# sensor_board_v0_51.net
KiCad netlist of a schematic drawn in EAGLE
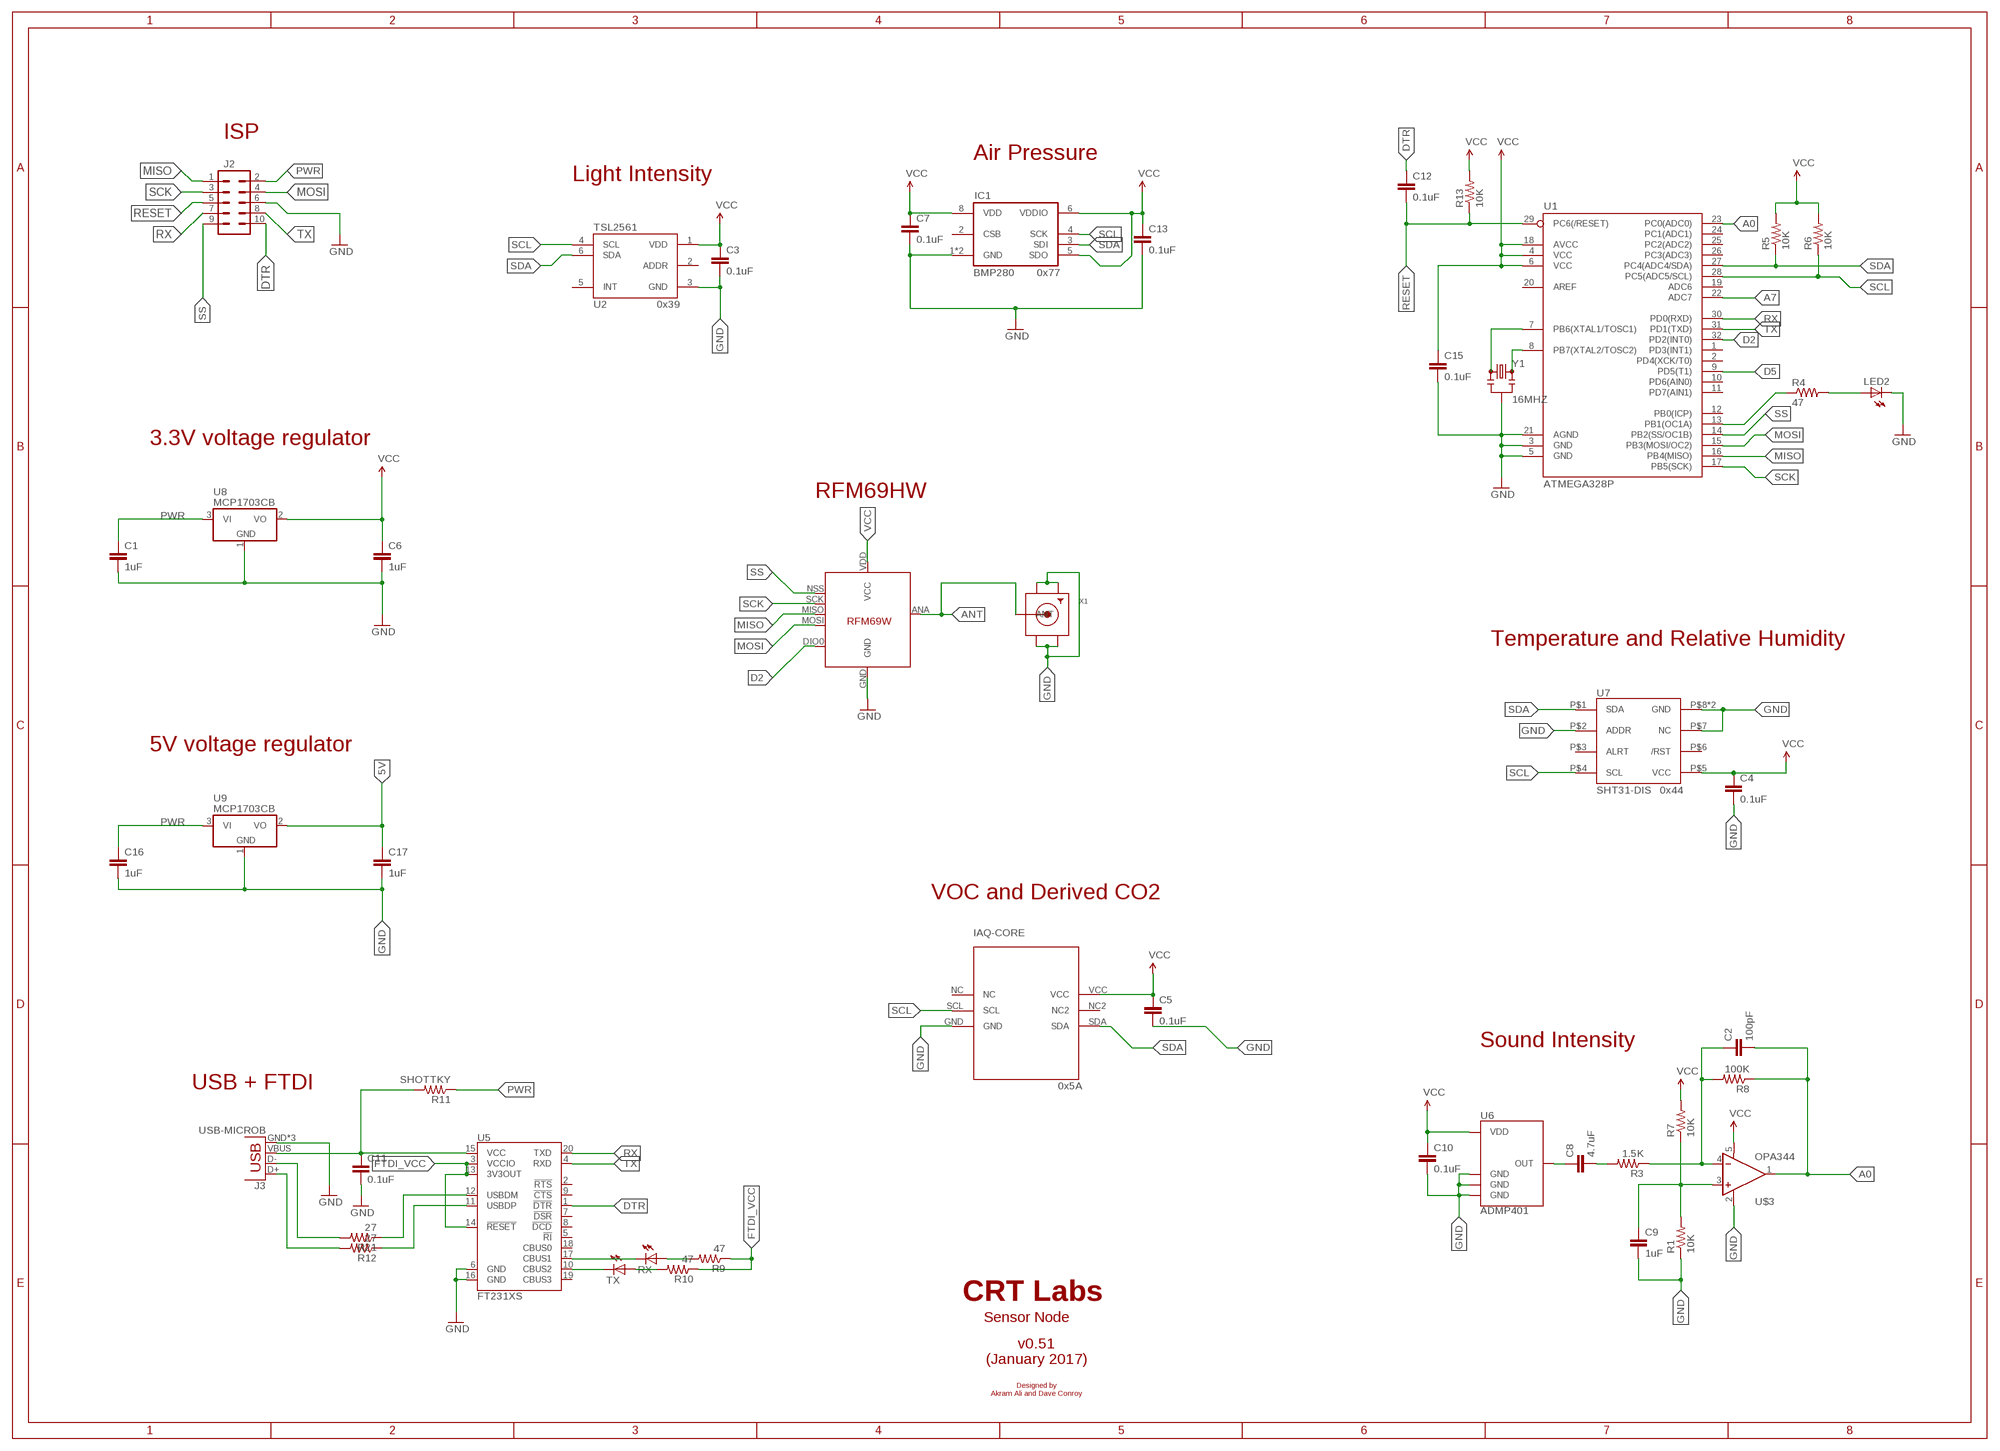
[diagram p0: schematic, sheet 1]

(export (version "E")
  (design (tool "Eeschema 10.0.6"))
  (components
    (comp (ref "C1")
      (value "1uF")
      (footprint "eagle-import:0805")
      (libsource (lib "eagle-import") (part "CAP0805"))
    )
    (comp (ref "C2")
      (value "100pF")
      (footprint "eagle-import:0805")
      (libsource (lib "eagle-import") (part "CAP0805"))
    )
    (comp (ref "C3")
      (value "0.1uF")
      (footprint "eagle-import:0805")
      (libsource (lib "eagle-import") (part "SparkFun-Passives_CAP0805"))
    )
    (comp (ref "C4")
      (value "0.1uF")
      (footprint "eagle-import:0805")
      (libsource (lib "eagle-import") (part "SparkFun-Passives_CAP0805"))
    )
    (comp (ref "C5")
      (value "0.1uF")
      (footprint "eagle-import:0805")
      (libsource (lib "eagle-import") (part "SparkFun-Passives_CAP0805"))
    )
    (comp (ref "C6")
      (value "1uF")
      (footprint "eagle-import:0805")
      (libsource (lib "eagle-import") (part "CAP0805"))
    )
    (comp (ref "C7")
      (value "0.1uF")
      (footprint "eagle-import:0805")
      (libsource (lib "eagle-import") (part "SparkFun-Passives_CAP0805"))
    )
    (comp (ref "C8")
      (value "4.7uF")
      (footprint "eagle-import:0805")
      (libsource (lib "eagle-import") (part "CAP0805"))
    )
    (comp (ref "C9")
      (value "1uF")
      (footprint "eagle-import:0805")
      (libsource (lib "eagle-import") (part "CAP0805"))
    )
    (comp (ref "C10")
      (value "0.1uF")
      (footprint "eagle-import:0805")
      (libsource (lib "eagle-import") (part "CAP0805"))
    )
    (comp (ref "C11")
      (value "0.1uF")
      (footprint "eagle-import:0805")
      (libsource (lib "eagle-import") (part "CAP0805"))
    )
    (comp (ref "C12")
      (value "0.1uF")
      (footprint "eagle-import:0805")
      (libsource (lib "eagle-import") (part "SparkFun-Passives_CAP0805"))
    )
    (comp (ref "C13")
      (value "0.1uF")
      (footprint "eagle-import:0805")
      (libsource (lib "eagle-import") (part "SparkFun-Passives_CAP0805"))
    )
    (comp (ref "C15")
      (value "0.1uF")
      (footprint "eagle-import:0805")
      (libsource (lib "eagle-import") (part "SparkFun-Passives_CAP0805"))
    )
    (comp (ref "C16")
      (value "1uF")
      (footprint "eagle-import:0805")
      (libsource (lib "eagle-import") (part "CAP0805"))
    )
    (comp (ref "C17")
      (value "1uF")
      (footprint "eagle-import:0805")
      (libsource (lib "eagle-import") (part "CAP0805"))
    )
    (comp (ref "IAQ-CORE")
      (value "IAQ-CORE")
      (footprint "eagle-import:IAQ-CORE")
      (fields (field (name "MPN") "IAQ CORE"))
      (libsource (lib "eagle-import") (part "IAQ-CORE"))
    )
    (comp (ref "IC1")
      (value "BMP280")
      (footprint "eagle-import:BMP280")
      (libsource (lib "eagle-import") (part "BMP280"))
    )
    (comp (ref "J2")
      (value "M05X2PTH")
      (footprint "eagle-import:AVR_ICSP")
      (libsource (lib "eagle-import") (part "M05X2PTH"))
    )
    (comp (ref "J3")
      (value "USB-MICROB")
      (footprint "eagle-import:USB-MICROB")
      (libsource (lib "eagle-import") (part "USB-MICROB"))
    )
    (comp (ref "LED2")
      (value "LEDCHIPLED_0805")
      (footprint "eagle-import:CHIPLED_0805")
      (libsource (lib "eagle-import") (part "LEDCHIPLED_0805"))
    )
    (comp (ref "R1")
      (value "10K")
      (footprint "eagle-import:0805")
      (libsource (lib "eagle-import") (part "RESISTOR0805-RES"))
    )
    (comp (ref "R3")
      (value "1.5K")
      (footprint "eagle-import:0805")
      (libsource (lib "eagle-import") (part "RESISTOR0805-RES"))
    )
    (comp (ref "R4")
      (value "47")
      (footprint "eagle-import:0805")
      (libsource (lib "eagle-import") (part "SparkFun-Resistors_RESISTOR0805-RES"))
    )
    (comp (ref "R5")
      (value "10K")
      (footprint "eagle-import:0805")
      (libsource (lib "eagle-import") (part "SparkFun-Resistors_RESISTOR0805-RES"))
    )
    (comp (ref "R6")
      (value "10K")
      (footprint "eagle-import:0805")
      (libsource (lib "eagle-import") (part "SparkFun-Resistors_RESISTOR0805-RES"))
    )
    (comp (ref "R7")
      (value "10K")
      (footprint "eagle-import:0805")
      (libsource (lib "eagle-import") (part "RESISTOR0805-RES"))
    )
    (comp (ref "R8")
      (value "100K")
      (footprint "eagle-import:0805")
      (libsource (lib "eagle-import") (part "RESISTOR0805-RES"))
    )
    (comp (ref "R9")
      (value "47")
      (footprint "eagle-import:0805")
      (libsource (lib "eagle-import") (part "RESISTOR0805-RES"))
    )
    (comp (ref "R10")
      (value "47")
      (footprint "eagle-import:0805")
      (libsource (lib "eagle-import") (part "RESISTOR0805-RES"))
    )
    (comp (ref "R11")
      (value "SHOTTKY")
      (footprint "eagle-import:0805")
      (libsource (lib "eagle-import") (part "RESISTOR0805-RES"))
    )
    (comp (ref "R12")
      (value "27")
      (footprint "eagle-import:0805")
      (libsource (lib "eagle-import") (part "RESISTOR0805-RES"))
    )
    (comp (ref "R13")
      (value "10K")
      (footprint "eagle-import:0805")
      (libsource (lib "eagle-import") (part "RESISTOR0805-RES"))
    )
    (comp (ref "R21")
      (value "27")
      (footprint "eagle-import:0805")
      (libsource (lib "eagle-import") (part "RESISTOR0805-RES"))
    )
    (comp (ref "RX")
      (value "LEDCHIPLED_0805")
      (footprint "eagle-import:CHIPLED_0805")
      (libsource (lib "eagle-import") (part "LEDCHIPLED_0805"))
    )
    (comp (ref "TX")
      (value "LEDCHIPLED_0805")
      (footprint "eagle-import:CHIPLED_0805")
      (libsource (lib "eagle-import") (part "LEDCHIPLED_0805"))
    )
    (comp (ref "U$3")
      (value "OPA344")
      (footprint "eagle-import:SOT23-5")
      (libsource (lib "eagle-import") (part "OPA344"))
    )
    (comp (ref "U$4")
      (value "RFM69HW")
      (footprint "eagle-import:LOWPOWERLAB_RFM69W-MINPADS")
      (libsource (lib "eagle-import") (part "LOWPOWERLAB_RFM69"))
    )
    (comp (ref "U1")
      (value "ATMEGA328P")
      (footprint "eagle-import:TQFP32-08")
      (fields (field (name "MPN") "ATMEGA328PB-AU"))
      (libsource (lib "eagle-import") (part "ATMEGA328P_TQFP"))
    )
    (comp (ref "U2")
      (value "TSL2561")
      (footprint "eagle-import:FN-6")
      (fields (field (name "MANF") "AMS-TAOS-USA-Inc.") (field (name "MPN") "TSL2561FN"))
      (libsource (lib "eagle-import") (part "TSL2561FN"))
    )
    (comp (ref "U5")
      (value "FT231XS")
      (footprint "eagle-import:SSOP20_L")
      (libsource (lib "eagle-import") (part "FT231XS"))
    )
    (comp (ref "U6")
      (value "ADMP401")
      (footprint "eagle-import:ADMP401")
      (libsource (lib "eagle-import") (part "ADMP401"))
    )
    (comp (ref "U7")
      (value "SHT31-DIS")
      (footprint "eagle-import:SHT3X")
      (fields (field (name "MPN") "SHT31-DIS-B"))
      (libsource (lib "eagle-import") (part "SHT31-DIS"))
    )
    (comp (ref "U8")
      (value "MCP1703CB")
      (footprint "eagle-import:SOT23")
      (fields (field (name "MPN") "MCP1703T-2502E/CB"))
      (libsource (lib "eagle-import") (part "MCP1703CB"))
    )
    (comp (ref "U9")
      (value "MCP1703CB")
      (footprint "eagle-import:SOT23")
      (fields (field (name "MPN") "MCP1703T-2502E/CB"))
      (libsource (lib "eagle-import") (part "MCP1703CB"))
    )
    (comp (ref "X1")
      (value "SMACONNECTOR_EDGE")
      (footprint "eagle-import:SMA_EDGELAUNCH")
      (libsource (lib "eagle-import") (part "SMACONNECTOR_EDGE"))
    )
    (comp (ref "Y1")
      (value "16MHZ")
      (footprint "eagle-import:RESONATOR-SMD")
      (libsource (lib "eagle-import") (part "RESONATOR16MHZ"))
    )
  )
  (nets
    (net (code "1") (name "5V") (class "Default")
      (node (ref "C17") (pin "1") (pinfunction "1_1") (pintype "passive"))
      (node (ref "U9") (pin "2") (pinfunction "VO_2") (pintype "passive"))
    )
    (net (code "2") (name "A0") (class "Default")
      (node (ref "C2") (pin "2") (pinfunction "2_2") (pintype "passive"))
      (node (ref "R8") (pin "1") (pinfunction "1_1") (pintype "passive"))
      (node (ref "U$3") (pin "1") (pinfunction "OUT_1") (pintype "output"))
      (node (ref "U1") (pin "23") (pinfunction "PC0(ADC0)_23") (pintype "bidirectional"))
    )
    (net (code "3") (name "A7") (class "Default")
      (node (ref "U1") (pin "22") (pinfunction "ADC7_22") (pintype "bidirectional"))
    )
    (net (code "4") (name "ANT") (class "Default")
      (node (ref "U$4") (pin "ANA") (pinfunction "ANT_ANA") (pintype "passive"))
      (node (ref "X1") (pin "P") (pinfunction "ANT_P") (pintype "bidirectional"))
    )
    (net (code "5") (name "D2") (class "Default")
      (node (ref "U$4") (pin "DIO0") (pinfunction "DIO0_DIO0") (pintype "open_collector"))
      (node (ref "U1") (pin "32") (pinfunction "PD2(INT0)_32") (pintype "bidirectional"))
    )
    (net (code "6") (name "D5") (class "Default")
      (node (ref "U1") (pin "9") (pinfunction "PD5(T1)_9") (pintype "bidirectional"))
    )
    (net (code "7") (name "DTR") (class "Default")
      (node (ref "C12") (pin "1") (pinfunction "1_1") (pintype "passive"))
      (node (ref "J2") (pin "10") (pinfunction "10_10") (pintype "passive"))
      (node (ref "U5") (pin "1") (pinfunction "~{DTR}_1") (pintype "bidirectional"))
    )
    (net (code "8") (name "FTDI_VCC") (class "Default")
      (node (ref "R10") (pin "1") (pinfunction "1_1") (pintype "passive"))
      (node (ref "R9") (pin "1") (pinfunction "1_1") (pintype "passive"))
      (node (ref "U5") (pin "13") (pinfunction "3V3OUT_13") (pintype "bidirectional"))
      (node (ref "U5") (pin "14") (pinfunction "~{RESET}_14") (pintype "bidirectional"))
      (node (ref "U5") (pin "3") (pinfunction "VCCIO_3") (pintype "bidirectional"))
    )
    (net (code "9") (name "GND") (class "Default")
      (node (ref "C1") (pin "2") (pinfunction "2_2") (pintype "passive"))
      (node (ref "C10") (pin "2") (pinfunction "2_2") (pintype "passive"))
      (node (ref "C11") (pin "2") (pinfunction "2_2") (pintype "passive"))
      (node (ref "C13") (pin "2") (pinfunction "2_2") (pintype "passive"))
      (node (ref "C15") (pin "2") (pinfunction "2_2") (pintype "passive"))
      (node (ref "C16") (pin "2") (pinfunction "2_2") (pintype "passive"))
      (node (ref "C17") (pin "2") (pinfunction "2_2") (pintype "passive"))
      (node (ref "C3") (pin "2") (pinfunction "2_2") (pintype "passive"))
      (node (ref "C4") (pin "2") (pinfunction "2_2") (pintype "passive"))
      (node (ref "C5") (pin "2") (pinfunction "2_2") (pintype "passive"))
      (node (ref "C6") (pin "2") (pinfunction "2_2") (pintype "passive"))
      (node (ref "C7") (pin "2") (pinfunction "2_2") (pintype "passive"))
      (node (ref "C9") (pin "2") (pinfunction "2_2") (pintype "passive"))
      (node (ref "IAQ-CORE") (pin "GND") (pinfunction "GND_GND") (pintype "bidirectional"))
      (node (ref "IC1") (pin "1") (pinfunction "GND_1") (pintype "power_in"))
      (node (ref "IC1") (pin "7") (pinfunction "GND_7") (pintype "power_in"))
      (node (ref "J2") (pin "6") (pinfunction "6_6") (pintype "passive"))
      (node (ref "J3") (pin "GND") (pinfunction "GND_GND") (pintype "bidirectional"))
      (node (ref "J3") (pin "MT1") (pinfunction "GND_MT1") (pintype "bidirectional"))
      (node (ref "J3") (pin "MT2") (pinfunction "GND_MT2") (pintype "bidirectional"))
      (node (ref "LED2") (pin "C") (pinfunction "C_C") (pintype "passive"))
      (node (ref "R1") (pin "1") (pinfunction "1_1") (pintype "passive"))
      (node (ref "U$3") (pin "2") (pinfunction "V-_2") (pintype "power_in"))
      (node (ref "U$4") (pin "GND") (pinfunction "GND_GND") (pintype "power_in"))
      (node (ref "U1") (pin "21") (pinfunction "AGND_21") (pintype "bidirectional"))
      (node (ref "U1") (pin "3") (pinfunction "GND_3") (pintype "bidirectional"))
      (node (ref "U1") (pin "5") (pinfunction "GND_5") (pintype "bidirectional"))
      (node (ref "U2") (pin "3") (pinfunction "GND_3") (pintype "power_in"))
      (node (ref "U5") (pin "16") (pinfunction "GND_16") (pintype "bidirectional"))
      (node (ref "U5") (pin "6") (pinfunction "GND_6") (pintype "bidirectional"))
      (node (ref "U6") (pin "2") (pinfunction "GND_2") (pintype "bidirectional"))
      (node (ref "U6") (pin "4") (pinfunction "GND_4") (pintype "bidirectional"))
      (node (ref "U6") (pin "6") (pinfunction "GND_6") (pintype "bidirectional"))
      (node (ref "U7") (pin "P$2") (pinfunction "ADDR_P$2") (pintype "bidirectional"))
      (node (ref "U7") (pin "P$7") (pinfunction "NC_P$7") (pintype "bidirectional"))
      (node (ref "U7") (pin "P$8") (pinfunction "GND_P$8") (pintype "bidirectional"))
      (node (ref "U7") (pin "PAD") (pinfunction "GND_PAD") (pintype "bidirectional"))
      (node (ref "U8") (pin "1") (pinfunction "GND_1") (pintype "passive"))
      (node (ref "U9") (pin "1") (pinfunction "GND_1") (pintype "passive"))
      (node (ref "X1") (pin "GND@1") (pinfunction "GND4_GND@1") (pintype "power_in"))
      (node (ref "X1") (pin "GND@2") (pinfunction "GND3_GND@2") (pintype "power_in"))
      (node (ref "X1") (pin "GND@3") (pinfunction "GND2_GND@3") (pintype "power_in"))
      (node (ref "X1") (pin "GND@4") (pinfunction "GND1_GND@4") (pintype "power_in"))
      (node (ref "Y1") (pin "2") (pinfunction "2_2") (pintype "passive"))
    )
    (net (code "10") (name "MISO") (class "Default")
      (node (ref "J2") (pin "1") (pinfunction "1_1") (pintype "passive"))
      (node (ref "U$4") (pin "MISO") (pinfunction "MISO_MISO") (pintype "input"))
      (node (ref "U1") (pin "16") (pinfunction "PB4(MISO)_16") (pintype "bidirectional"))
    )
    (net (code "11") (name "MOSI") (class "Default")
      (node (ref "J2") (pin "4") (pinfunction "4_4") (pintype "passive"))
      (node (ref "U$4") (pin "MOSI") (pinfunction "MOSI_MOSI") (pintype "output"))
      (node (ref "U1") (pin "15") (pinfunction "PB3(MOSI/OC2)_15") (pintype "bidirectional"))
    )
    (net (code "12") (name "Net-(C8-Pad2)") (class "Default")
      (node (ref "C8") (pin "2") (pinfunction "2_2") (pintype "passive"))
      (node (ref "R3") (pin "2") (pinfunction "2_2") (pintype "passive"))
    )
    (net (code "13") (name "Net-(J3-PadD+)") (class "Default")
      (node (ref "J3") (pin "D+") (pinfunction "D+_D+") (pintype "bidirectional"))
      (node (ref "R12") (pin "2") (pinfunction "2_2") (pintype "passive"))
    )
    (net (code "14") (name "Net-(J3-PadD-)") (class "Default")
      (node (ref "J3") (pin "D-") (pinfunction "D-_D-") (pintype "bidirectional"))
      (node (ref "R21") (pin "2") (pinfunction "2_2") (pintype "passive"))
    )
    (net (code "15") (name "Net-(LED2-PadA)") (class "Default")
      (node (ref "LED2") (pin "A") (pinfunction "A_A") (pintype "passive"))
      (node (ref "R4") (pin "2") (pinfunction "2_2") (pintype "passive"))
    )
    (net (code "16") (name "Net-(R9-Pad2)") (class "Default")
      (node (ref "R9") (pin "2") (pinfunction "2_2") (pintype "passive"))
      (node (ref "RX") (pin "A") (pinfunction "A_A") (pintype "passive"))
    )
    (net (code "17") (name "Net-(R10-Pad2)") (class "Default")
      (node (ref "R10") (pin "2") (pinfunction "2_2") (pintype "passive"))
      (node (ref "TX") (pin "A") (pinfunction "A_A") (pintype "passive"))
    )
    (net (code "18") (name "Net-(U$3-+IN)") (class "Default")
      (node (ref "C9") (pin "1") (pinfunction "1_1") (pintype "passive"))
      (node (ref "R1") (pin "2") (pinfunction "2_2") (pintype "passive"))
      (node (ref "R7") (pin "1") (pinfunction "1_1") (pintype "passive"))
      (node (ref "U$3") (pin "3") (pinfunction "+IN_3") (pintype "input"))
    )
    (net (code "19") (name "Net-(U$3--IN)") (class "Default")
      (node (ref "C2") (pin "1") (pinfunction "1_1") (pintype "passive"))
      (node (ref "R3") (pin "1") (pinfunction "1_1") (pintype "passive"))
      (node (ref "R8") (pin "2") (pinfunction "2_2") (pintype "passive"))
      (node (ref "U$3") (pin "4") (pinfunction "-IN_4") (pintype "input"))
    )
    (net (code "20") (name "Net-(U1-PB1(OC1A))") (class "Default")
      (node (ref "R4") (pin "1") (pinfunction "1_1") (pintype "passive"))
      (node (ref "U1") (pin "13") (pinfunction "PB1(OC1A)_13") (pintype "bidirectional"))
    )
    (net (code "21") (name "Net-(U1-PB6(XTAL1{slash}TOSC1))") (class "Default")
      (node (ref "U1") (pin "7") (pinfunction "PB6(XTAL1/TOSC1)_7") (pintype "bidirectional"))
      (node (ref "Y1") (pin "1") (pinfunction "1_1") (pintype "passive"))
    )
    (net (code "22") (name "Net-(U1-PB7(XTAL2{slash}TOSC2))") (class "Default")
      (node (ref "U1") (pin "8") (pinfunction "PB7(XTAL2/TOSC2)_8") (pintype "bidirectional"))
      (node (ref "Y1") (pin "3") (pinfunction "3_3") (pintype "passive"))
    )
    (net (code "23") (name "Net-(U5-CBUS1)") (class "Default")
      (node (ref "RX") (pin "C") (pinfunction "C_C") (pintype "passive"))
      (node (ref "U5") (pin "17") (pinfunction "CBUS1_17") (pintype "bidirectional"))
    )
    (net (code "24") (name "Net-(U5-CBUS2)") (class "Default")
      (node (ref "TX") (pin "C") (pinfunction "C_C") (pintype "passive"))
      (node (ref "U5") (pin "10") (pinfunction "CBUS2_10") (pintype "bidirectional"))
    )
    (net (code "25") (name "Net-(U5-USBDM)") (class "Default")
      (node (ref "R21") (pin "1") (pinfunction "1_1") (pintype "passive"))
      (node (ref "U5") (pin "12") (pinfunction "USBDM_12") (pintype "bidirectional"))
    )
    (net (code "26") (name "Net-(U5-USBDP)") (class "Default")
      (node (ref "R12") (pin "1") (pinfunction "1_1") (pintype "passive"))
      (node (ref "U5") (pin "11") (pinfunction "USBDP_11") (pintype "bidirectional"))
    )
    (net (code "27") (name "Net-(U5-VCC)") (class "Default")
      (node (ref "C11") (pin "1") (pinfunction "1_1") (pintype "passive"))
      (node (ref "J3") (pin "VBUS") (pinfunction "VBUS_VBUS") (pintype "bidirectional"))
      (node (ref "R11") (pin "2") (pinfunction "2_2") (pintype "passive"))
      (node (ref "U5") (pin "15") (pinfunction "VCC_15") (pintype "bidirectional"))
    )
    (net (code "28") (name "Net-(U6-OUT)") (class "Default")
      (node (ref "C8") (pin "1") (pinfunction "1_1") (pintype "passive"))
      (node (ref "U6") (pin "1") (pinfunction "OUT_1") (pintype "bidirectional"))
    )
    (net (code "29") (name "PWR") (class "Default")
      (node (ref "C1") (pin "1") (pinfunction "1_1") (pintype "passive"))
      (node (ref "C16") (pin "1") (pinfunction "1_1") (pintype "passive"))
      (node (ref "J2") (pin "2") (pinfunction "2_2") (pintype "passive"))
      (node (ref "R11") (pin "1") (pinfunction "1_1") (pintype "passive"))
      (node (ref "U8") (pin "3") (pinfunction "VI_3") (pintype "input"))
      (node (ref "U9") (pin "3") (pinfunction "VI_3") (pintype "input"))
    )
    (net (code "30") (name "RESET") (class "Default")
      (node (ref "C12") (pin "2") (pinfunction "2_2") (pintype "passive"))
      (node (ref "J2") (pin "5") (pinfunction "5_5") (pintype "passive"))
      (node (ref "R13") (pin "1") (pinfunction "1_1") (pintype "passive"))
      (node (ref "U1") (pin "29") (pinfunction "PC6(/RESET)_29") (pintype "bidirectional"))
    )
    (net (code "31") (name "RX") (class "Default")
      (node (ref "J2") (pin "7") (pinfunction "7_7") (pintype "passive"))
      (node (ref "U1") (pin "30") (pinfunction "PD0(RXD)_30") (pintype "bidirectional"))
      (node (ref "U5") (pin "20") (pinfunction "TXD_20") (pintype "bidirectional"))
    )
    (net (code "32") (name "SCK") (class "Default")
      (node (ref "J2") (pin "3") (pinfunction "3_3") (pintype "passive"))
      (node (ref "U$4") (pin "SCK") (pinfunction "SCK_SCK") (pintype "input"))
      (node (ref "U1") (pin "17") (pinfunction "PB5(SCK)_17") (pintype "bidirectional"))
    )
    (net (code "33") (name "SCL") (class "Default")
      (node (ref "IAQ-CORE") (pin "SCL") (pinfunction "SCL_SCL") (pintype "bidirectional"))
      (node (ref "IC1") (pin "4") (pinfunction "SCK_4") (pintype "bidirectional"))
      (node (ref "R6") (pin "1") (pinfunction "1_1") (pintype "passive"))
      (node (ref "U1") (pin "28") (pinfunction "PC5(ADC5/SCL)_28") (pintype "bidirectional"))
      (node (ref "U2") (pin "4") (pinfunction "SCL_4") (pintype "input"))
      (node (ref "U7") (pin "P$4") (pinfunction "SCL_P$4") (pintype "bidirectional"))
    )
    (net (code "34") (name "SDA") (class "Default")
      (node (ref "IAQ-CORE") (pin "SDA") (pinfunction "SDA_SDA") (pintype "bidirectional"))
      (node (ref "IC1") (pin "3") (pinfunction "SDI_3") (pintype "bidirectional"))
      (node (ref "R5") (pin "1") (pinfunction "1_1") (pintype "passive"))
      (node (ref "U1") (pin "27") (pinfunction "PC4(ADC4/SDA)_27") (pintype "bidirectional"))
      (node (ref "U2") (pin "6") (pinfunction "SDA_6") (pintype "bidirectional"))
      (node (ref "U7") (pin "P$1") (pinfunction "SDA_P$1") (pintype "bidirectional"))
    )
    (net (code "35") (name "SS") (class "Default")
      (node (ref "J2") (pin "9") (pinfunction "9_9") (pintype "passive"))
      (node (ref "U$4") (pin "NSS") (pinfunction "SEL_NSS") (pintype "input"))
      (node (ref "U1") (pin "14") (pinfunction "PB2(SS/OC1B)_14") (pintype "bidirectional"))
    )
    (net (code "36") (name "TX") (class "Default")
      (node (ref "J2") (pin "8") (pinfunction "8_8") (pintype "passive"))
      (node (ref "U1") (pin "31") (pinfunction "PD1(TXD)_31") (pintype "bidirectional"))
      (node (ref "U5") (pin "4") (pinfunction "RXD_4") (pintype "bidirectional"))
    )
    (net (code "37") (name "VCC") (class "Default")
      (node (ref "C10") (pin "1") (pinfunction "1_1") (pintype "passive"))
      (node (ref "C13") (pin "1") (pinfunction "1_1") (pintype "passive"))
      (node (ref "C15") (pin "1") (pinfunction "1_1") (pintype "passive"))
      (node (ref "C3") (pin "1") (pinfunction "1_1") (pintype "passive"))
      (node (ref "C4") (pin "1") (pinfunction "1_1") (pintype "passive"))
      (node (ref "C5") (pin "1") (pinfunction "1_1") (pintype "passive"))
      (node (ref "C6") (pin "1") (pinfunction "1_1") (pintype "passive"))
      (node (ref "C7") (pin "1") (pinfunction "1_1") (pintype "passive"))
      (node (ref "IAQ-CORE") (pin "VCC") (pinfunction "VCC_VCC") (pintype "bidirectional"))
      (node (ref "IC1") (pin "5") (pinfunction "SDO_5") (pintype "input"))
      (node (ref "IC1") (pin "6") (pinfunction "VDDIO_6") (pintype "power_in"))
      (node (ref "IC1") (pin "8") (pinfunction "VDD_8") (pintype "power_in"))
      (node (ref "R13") (pin "2") (pinfunction "2_2") (pintype "passive"))
      (node (ref "R5") (pin "2") (pinfunction "2_2") (pintype "passive"))
      (node (ref "R6") (pin "2") (pinfunction "2_2") (pintype "passive"))
      (node (ref "R7") (pin "2") (pinfunction "2_2") (pintype "passive"))
      (node (ref "U$3") (pin "5") (pinfunction "V+_5") (pintype "power_in"))
      (node (ref "U$4") (pin "VDD") (pinfunction "VCC_VDD") (pintype "power_in"))
      (node (ref "U1") (pin "18") (pinfunction "AVCC_18") (pintype "bidirectional"))
      (node (ref "U1") (pin "4") (pinfunction "VCC_4") (pintype "bidirectional"))
      (node (ref "U1") (pin "6") (pinfunction "VCC_6") (pintype "bidirectional"))
      (node (ref "U2") (pin "1") (pinfunction "VDD_1") (pintype "power_in"))
      (node (ref "U6") (pin "5") (pinfunction "VDD_5") (pintype "bidirectional"))
      (node (ref "U7") (pin "P$5") (pinfunction "VCC_P$5") (pintype "bidirectional"))
      (node (ref "U8") (pin "2") (pinfunction "VO_2") (pintype "passive"))
    )
    (net (code "38") (name "unconnected-(IAQ-CORE-PadNC)") (class "Default")
      (node (ref "IAQ-CORE") (pin "NC") (pinfunction "NC_NC") (pintype "bidirectional"))
    )
    (net (code "39") (name "unconnected-(IAQ-CORE-PadNC2)") (class "Default")
      (node (ref "IAQ-CORE") (pin "NC2") (pinfunction "NC2_NC2") (pintype "bidirectional"))
    )
    (net (code "40") (name "unconnected-(IC1-CSB-Pad2)") (class "Default")
      (node (ref "IC1") (pin "2") (pinfunction "CSB_2") (pintype "input"))
    )
    (net (code "41") (name "unconnected-(U1-ADC6-Pad19)") (class "Default")
      (node (ref "U1") (pin "19") (pinfunction "ADC6_19") (pintype "bidirectional"))
    )
    (net (code "42") (name "unconnected-(U1-AREF-Pad20)") (class "Default")
      (node (ref "U1") (pin "20") (pinfunction "AREF_20") (pintype "bidirectional"))
    )
    (net (code "43") (name "unconnected-(U1-PB0(ICP)-Pad12)") (class "Default")
      (node (ref "U1") (pin "12") (pinfunction "PB0(ICP)_12") (pintype "bidirectional"))
    )
    (net (code "44") (name "unconnected-(U1-PC1(ADC1)-Pad24)") (class "Default")
      (node (ref "U1") (pin "24") (pinfunction "PC1(ADC1)_24") (pintype "bidirectional"))
    )
    (net (code "45") (name "unconnected-(U1-PC2(ADC2)-Pad25)") (class "Default")
      (node (ref "U1") (pin "25") (pinfunction "PC2(ADC2)_25") (pintype "bidirectional"))
    )
    (net (code "46") (name "unconnected-(U1-PC3(ADC3)-Pad26)") (class "Default")
      (node (ref "U1") (pin "26") (pinfunction "PC3(ADC3)_26") (pintype "bidirectional"))
    )
    (net (code "47") (name "unconnected-(U1-PD3(INT1)-Pad1)") (class "Default")
      (node (ref "U1") (pin "1") (pinfunction "PD3(INT1)_1") (pintype "bidirectional"))
    )
    (net (code "48") (name "unconnected-(U1-PD4(XCK{slash}T0)-Pad2)") (class "Default")
      (node (ref "U1") (pin "2") (pinfunction "PD4(XCK/T0)_2") (pintype "bidirectional"))
    )
    (net (code "49") (name "unconnected-(U1-PD6(AIN0)-Pad10)") (class "Default")
      (node (ref "U1") (pin "10") (pinfunction "PD6(AIN0)_10") (pintype "bidirectional"))
    )
    (net (code "50") (name "unconnected-(U1-PD7(AIN1)-Pad11)") (class "Default")
      (node (ref "U1") (pin "11") (pinfunction "PD7(AIN1)_11") (pintype "bidirectional"))
    )
    (net (code "51") (name "unconnected-(U2-ADDR-Pad2)") (class "Default")
      (node (ref "U2") (pin "2") (pinfunction "ADDR_2") (pintype "input"))
    )
    (net (code "52") (name "unconnected-(U2-INT-Pad5)") (class "Default")
      (node (ref "U2") (pin "5") (pinfunction "INT_5") (pintype "output"))
    )
    (net (code "53") (name "unconnected-(U5-CBUS0-Pad18)") (class "Default")
      (node (ref "U5") (pin "18") (pinfunction "CBUS0_18") (pintype "bidirectional"))
    )
    (net (code "54") (name "unconnected-(U5-CBUS3-Pad19)") (class "Default")
      (node (ref "U5") (pin "19") (pinfunction "CBUS3_19") (pintype "bidirectional"))
    )
    (net (code "55") (name "unconnected-(U5-~{CTS}-Pad9)") (class "Default")
      (node (ref "U5") (pin "9") (pinfunction "~{CTS}_9") (pintype "bidirectional"))
    )
    (net (code "56") (name "unconnected-(U5-~{DCD}-Pad8)") (class "Default")
      (node (ref "U5") (pin "8") (pinfunction "~{DCD}_8") (pintype "bidirectional"))
    )
    (net (code "57") (name "unconnected-(U5-~{DSR}-Pad7)") (class "Default")
      (node (ref "U5") (pin "7") (pinfunction "~{DSR}_7") (pintype "bidirectional"))
    )
    (net (code "58") (name "unconnected-(U5-~{RI}-Pad5)") (class "Default")
      (node (ref "U5") (pin "5") (pinfunction "~{RI}_5") (pintype "bidirectional"))
    )
    (net (code "59") (name "unconnected-(U5-~{RTS}-Pad2)") (class "Default")
      (node (ref "U5") (pin "2") (pinfunction "~{RTS}_2") (pintype "bidirectional"))
    )
    (net (code "60") (name "unconnected-(U7-ALRT-PadP$3)") (class "Default")
      (node (ref "U7") (pin "P$3") (pinfunction "ALRT_P$3") (pintype "bidirectional"))
    )
    (net (code "61") (name "unconnected-(U7-{slash}RST-PadP$6)") (class "Default")
      (node (ref "U7") (pin "P$6") (pinfunction "/RST_P$6") (pintype "bidirectional"))
    )
  )
)
